# downmixersA.net
KiCad netlist of a schematic drawn in Altium Designer
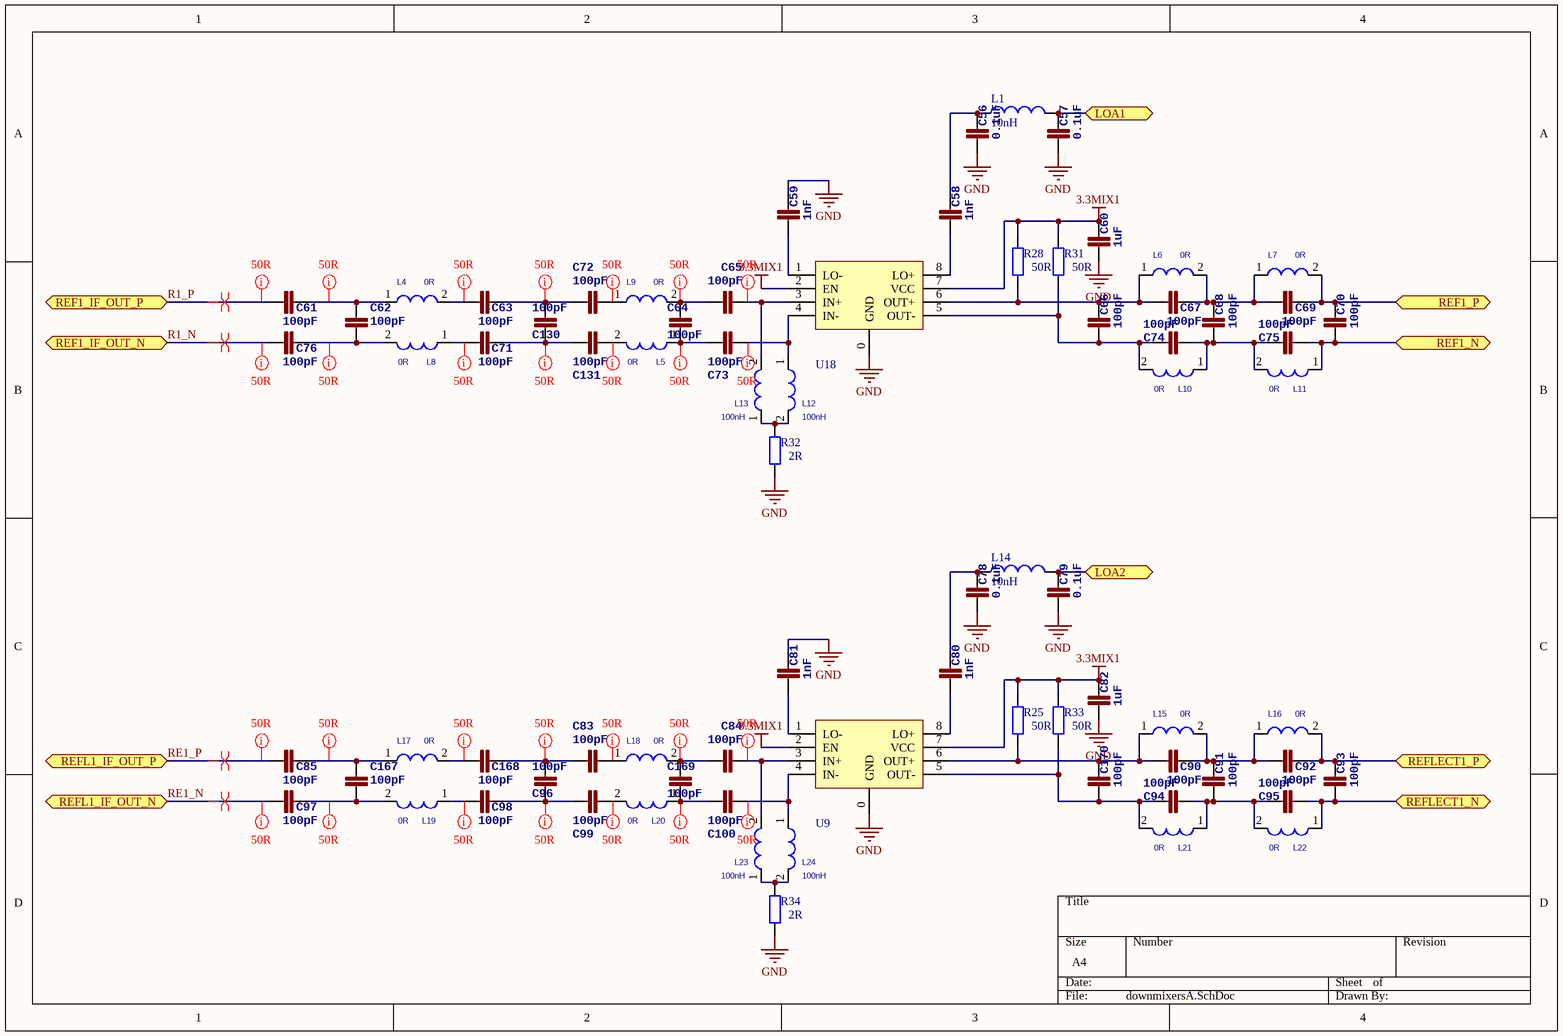
[diagram p0: downmixersA.SchDoc]

(export (version "E")
  (design (tool "Eeschema 10.0.6"))
  (components
    (comp (ref "C56")
      (value "0.1uF")
      (footprint "0402")
      (description "<b>Capacitor</b>\nStandard 0603 ceramic capacitor, and 0.1\" leaded capacitor.")
      (fields (field (name "PARTNO") "CC0402ZRY5V7BB104"))
      (libsource (lib "pixhawk2") (part "CAP0402-CAP"))
    )
    (comp (ref "C57")
      (value "0.1uF")
      (footprint "0402")
      (description "<b>Capacitor</b>\nStandard 0603 ceramic capacitor, and 0.1\" leaded capacitor.")
      (fields (field (name "PARTNO") "CC0402ZRY5V7BB104"))
      (libsource (lib "pixhawk2") (part "CAP0402-CAP"))
    )
    (comp (ref "C58")
      (value "1nF")
      (footprint "0402")
      (description "<b>Capacitor</b>\nStandard 0603 ceramic capacitor, and 0.1\" leaded capacitor.")
      (fields (field (name "PARTNO") "CC0402ZRY5V7BB104"))
      (libsource (lib "pixhawk2") (part "CAP0402-CAP"))
    )
    (comp (ref "C59")
      (value "1nF")
      (footprint "0402")
      (description "<b>Capacitor</b>\nStandard 0603 ceramic capacitor, and 0.1\" leaded capacitor.")
      (fields (field (name "PARTNO") "CC0402ZRY5V7BB104"))
      (libsource (lib "pixhawk2") (part "CAP0402-CAP"))
    )
    (comp (ref "C60")
      (value "1uF")
      (footprint "0402")
      (description "<b>Capacitor</b>\nStandard 0603 ceramic capacitor, and 0.1\" leaded capacitor.")
      (fields (field (name "PARTNO") "CC0402ZRY5V7BB104"))
      (libsource (lib "pixhawk2") (part "CAP0402-CAP"))
    )
    (comp (ref "C61")
      (value "100pF")
      (footprint "0402")
      (description "<b>Capacitor</b>\nStandard 0603 ceramic capacitor, and 0.1\" leaded capacitor.")
      (fields (field (name "PARTNO") "CC0402ZRY5V7BB104"))
      (libsource (lib "") (part "CAP0402-CAP_1"))
    )
    (comp (ref "C62")
      (value "100pF")
      (footprint "0402")
      (description "<b>Capacitor</b>\nStandard 0603 ceramic capacitor, and 0.1\" leaded capacitor.")
      (fields (field (name "PARTNO") "CC0402ZRY5V7BB104"))
      (libsource (lib "pixhawk2") (part "CAP0402-CAP"))
    )
    (comp (ref "C63")
      (value "100pF")
      (footprint "0402")
      (description "<b>Capacitor</b>\nStandard 0603 ceramic capacitor, and 0.1\" leaded capacitor.")
      (fields (field (name "PARTNO") "CC0402ZRY5V7BB104"))
      (libsource (lib "") (part "CAP0402-CAP_1"))
    )
    (comp (ref "C64")
      (value "100pF")
      (footprint "0402")
      (description "<b>Capacitor</b>\nStandard 0603 ceramic capacitor, and 0.1\" leaded capacitor.")
      (fields (field (name "PARTNO") "CC0402ZRY5V7BB104"))
      (libsource (lib "pixhawk2") (part "CAP0402-CAP"))
    )
    (comp (ref "C65")
      (value "100pF")
      (footprint "0402")
      (description "<b>Capacitor</b>\nStandard 0603 ceramic capacitor, and 0.1\" leaded capacitor.")
      (fields (field (name "PARTNO") "CC0402ZRY5V7BB104"))
      (libsource (lib "") (part "CAP0402-CAP_1"))
    )
    (comp (ref "C66")
      (value "100pF")
      (footprint "0402")
      (description "<b>Capacitor</b>\nStandard 0603 ceramic capacitor, and 0.1\" leaded capacitor.")
      (fields (field (name "PARTNO") "CC0402ZRY5V7BB104"))
      (libsource (lib "pixhawk2") (part "CAP0402-CAP"))
    )
    (comp (ref "C67")
      (value "100pF")
      (footprint "0402")
      (description "<b>Capacitor</b>\nStandard 0603 ceramic capacitor, and 0.1\" leaded capacitor.")
      (fields (field (name "PARTNO") "CC0402ZRY5V7BB104"))
      (libsource (lib "") (part "CAP0402-CAP_1"))
    )
    (comp (ref "C68")
      (value "100pF")
      (footprint "0402")
      (description "<b>Capacitor</b>\nStandard 0603 ceramic capacitor, and 0.1\" leaded capacitor.")
      (fields (field (name "PARTNO") "CC0402ZRY5V7BB104"))
      (libsource (lib "pixhawk2") (part "CAP0402-CAP"))
    )
    (comp (ref "C69")
      (value "100pF")
      (footprint "0402")
      (description "<b>Capacitor</b>\nStandard 0603 ceramic capacitor, and 0.1\" leaded capacitor.")
      (fields (field (name "PARTNO") "CC0402ZRY5V7BB104"))
      (libsource (lib "") (part "CAP0402-CAP_1"))
    )
    (comp (ref "C70")
      (value "100pF")
      (footprint "0402")
      (description "<b>Capacitor</b>\nStandard 0603 ceramic capacitor, and 0.1\" leaded capacitor.")
      (fields (field (name "PARTNO") "CC0402ZRY5V7BB104"))
      (libsource (lib "pixhawk2") (part "CAP0402-CAP"))
    )
    (comp (ref "C71")
      (value "100pF")
      (footprint "0402")
      (description "<b>Capacitor</b>\nStandard 0603 ceramic capacitor, and 0.1\" leaded capacitor.")
      (fields (field (name "PARTNO") "CC0402ZRY5V7BB104"))
      (libsource (lib "") (part "CAP0402-CAP_1"))
    )
    (comp (ref "C72")
      (value "100pF")
      (footprint "0402")
      (description "<b>Capacitor</b>\nStandard 0603 ceramic capacitor, and 0.1\" leaded capacitor.")
      (fields (field (name "PARTNO") "CC0402ZRY5V7BB104"))
      (libsource (lib "") (part "CAP0402-CAP_1"))
    )
    (comp (ref "C73")
      (value "100pF")
      (footprint "0402")
      (description "<b>Capacitor</b>\nStandard 0603 ceramic capacitor, and 0.1\" leaded capacitor.")
      (fields (field (name "PARTNO") "CC0402ZRY5V7BB104"))
      (libsource (lib "") (part "CAP0402-CAP_2"))
    )
    (comp (ref "C74")
      (value "100pF")
      (footprint "0402")
      (description "<b>Capacitor</b>\nStandard 0603 ceramic capacitor, and 0.1\" leaded capacitor.")
      (fields (field (name "PARTNO") "CC0402ZRY5V7BB104"))
      (libsource (lib "") (part "CAP0402-CAP_2"))
    )
    (comp (ref "C75")
      (value "100pF")
      (footprint "0402")
      (description "<b>Capacitor</b>\nStandard 0603 ceramic capacitor, and 0.1\" leaded capacitor.")
      (fields (field (name "PARTNO") "CC0402ZRY5V7BB104"))
      (libsource (lib "") (part "CAP0402-CAP_2"))
    )
    (comp (ref "C76")
      (value "100pF")
      (footprint "0402")
      (description "<b>Capacitor</b>\nStandard 0603 ceramic capacitor, and 0.1\" leaded capacitor.")
      (fields (field (name "PARTNO") "CC0402ZRY5V7BB104"))
      (libsource (lib "") (part "CAP0402-CAP_1"))
    )
    (comp (ref "C78")
      (value "0.1uF")
      (footprint "0402")
      (description "<b>Capacitor</b>\nStandard 0603 ceramic capacitor, and 0.1\" leaded capacitor.")
      (fields (field (name "PARTNO") "CC0402ZRY5V7BB104"))
      (libsource (lib "pixhawk2") (part "CAP0402-CAP"))
    )
    (comp (ref "C79")
      (value "0.1uF")
      (footprint "0402")
      (description "<b>Capacitor</b>\nStandard 0603 ceramic capacitor, and 0.1\" leaded capacitor.")
      (fields (field (name "PARTNO") "CC0402ZRY5V7BB104"))
      (libsource (lib "pixhawk2") (part "CAP0402-CAP"))
    )
    (comp (ref "C80")
      (value "1nF")
      (footprint "0402")
      (description "<b>Capacitor</b>\nStandard 0603 ceramic capacitor, and 0.1\" leaded capacitor.")
      (fields (field (name "PARTNO") "CC0402ZRY5V7BB104"))
      (libsource (lib "pixhawk2") (part "CAP0402-CAP"))
    )
    (comp (ref "C81")
      (value "1nF")
      (footprint "0402")
      (description "<b>Capacitor</b>\nStandard 0603 ceramic capacitor, and 0.1\" leaded capacitor.")
      (fields (field (name "PARTNO") "CC0402ZRY5V7BB104"))
      (libsource (lib "pixhawk2") (part "CAP0402-CAP"))
    )
    (comp (ref "C82")
      (value "1uF")
      (footprint "0402")
      (description "<b>Capacitor</b>\nStandard 0603 ceramic capacitor, and 0.1\" leaded capacitor.")
      (fields (field (name "PARTNO") "CC0402ZRY5V7BB104"))
      (libsource (lib "pixhawk2") (part "CAP0402-CAP"))
    )
    (comp (ref "C83")
      (value "100pF")
      (footprint "0402")
      (description "<b>Capacitor</b>\nStandard 0603 ceramic capacitor, and 0.1\" leaded capacitor.")
      (fields (field (name "PARTNO") "CC0402ZRY5V7BB104"))
      (libsource (lib "") (part "CAP0402-CAP_1"))
    )
    (comp (ref "C84")
      (value "100pF")
      (footprint "0402")
      (description "<b>Capacitor</b>\nStandard 0603 ceramic capacitor, and 0.1\" leaded capacitor.")
      (fields (field (name "PARTNO") "CC0402ZRY5V7BB104"))
      (libsource (lib "") (part "CAP0402-CAP_1"))
    )
    (comp (ref "C85")
      (value "100pF")
      (footprint "0402")
      (description "<b>Capacitor</b>\nStandard 0603 ceramic capacitor, and 0.1\" leaded capacitor.")
      (fields (field (name "PARTNO") "CC0402ZRY5V7BB104"))
      (libsource (lib "") (part "CAP0402-CAP_1"))
    )
    (comp (ref "C90")
      (value "100pF")
      (footprint "0402")
      (description "<b>Capacitor</b>\nStandard 0603 ceramic capacitor, and 0.1\" leaded capacitor.")
      (fields (field (name "PARTNO") "CC0402ZRY5V7BB104"))
      (libsource (lib "") (part "CAP0402-CAP_1"))
    )
    (comp (ref "C91")
      (value "100pF")
      (footprint "0402")
      (description "<b>Capacitor</b>\nStandard 0603 ceramic capacitor, and 0.1\" leaded capacitor.")
      (fields (field (name "PARTNO") "CC0402ZRY5V7BB104"))
      (libsource (lib "pixhawk2") (part "CAP0402-CAP"))
    )
    (comp (ref "C92")
      (value "100pF")
      (footprint "0402")
      (description "<b>Capacitor</b>\nStandard 0603 ceramic capacitor, and 0.1\" leaded capacitor.")
      (fields (field (name "PARTNO") "CC0402ZRY5V7BB104"))
      (libsource (lib "") (part "CAP0402-CAP_1"))
    )
    (comp (ref "C93")
      (value "100pF")
      (footprint "0402")
      (description "<b>Capacitor</b>\nStandard 0603 ceramic capacitor, and 0.1\" leaded capacitor.")
      (fields (field (name "PARTNO") "CC0402ZRY5V7BB104"))
      (libsource (lib "pixhawk2") (part "CAP0402-CAP"))
    )
    (comp (ref "C94")
      (value "100pF")
      (footprint "0402")
      (description "<b>Capacitor</b>\nStandard 0603 ceramic capacitor, and 0.1\" leaded capacitor.")
      (fields (field (name "PARTNO") "CC0402ZRY5V7BB104"))
      (libsource (lib "") (part "CAP0402-CAP_2"))
    )
    (comp (ref "C95")
      (value "100pF")
      (footprint "0402")
      (description "<b>Capacitor</b>\nStandard 0603 ceramic capacitor, and 0.1\" leaded capacitor.")
      (fields (field (name "PARTNO") "CC0402ZRY5V7BB104"))
      (libsource (lib "") (part "CAP0402-CAP_2"))
    )
    (comp (ref "C96")
      (value "100pF")
      (footprint "0402")
      (description "<b>Capacitor</b>\nStandard 0603 ceramic capacitor, and 0.1\" leaded capacitor.")
      (fields (field (name "PARTNO") "CC0402ZRY5V7BB104"))
      (libsource (lib "") (part "CAP0402-CAP_3"))
    )
    (comp (ref "C97")
      (value "100pF")
      (footprint "0402")
      (description "<b>Capacitor</b>\nStandard 0603 ceramic capacitor, and 0.1\" leaded capacitor.")
      (fields (field (name "PARTNO") "CC0402ZRY5V7BB104"))
      (libsource (lib "") (part "CAP0402-CAP_1"))
    )
    (comp (ref "C98")
      (value "100pF")
      (footprint "0402")
      (description "<b>Capacitor</b>\nStandard 0603 ceramic capacitor, and 0.1\" leaded capacitor.")
      (fields (field (name "PARTNO") "CC0402ZRY5V7BB104"))
      (libsource (lib "") (part "CAP0402-CAP_1"))
    )
    (comp (ref "C99")
      (value "100pF")
      (footprint "0402")
      (description "<b>Capacitor</b>\nStandard 0603 ceramic capacitor, and 0.1\" leaded capacitor.")
      (fields (field (name "PARTNO") "CC0402ZRY5V7BB104"))
      (libsource (lib "") (part "CAP0402-CAP_2"))
    )
    (comp (ref "C100")
      (value "100pF")
      (footprint "0402")
      (description "<b>Capacitor</b>\nStandard 0603 ceramic capacitor, and 0.1\" leaded capacitor.")
      (fields (field (name "PARTNO") "CC0402ZRY5V7BB104"))
      (libsource (lib "") (part "CAP0402-CAP_2"))
    )
    (comp (ref "C130")
      (value "100pF")
      (footprint "0402")
      (description "<b>Capacitor</b>\nStandard 0603 ceramic capacitor, and 0.1\" leaded capacitor.")
      (fields (field (name "PARTNO") "CC0402ZRY5V7BB104"))
      (libsource (lib "") (part "CAP0402-CAP_3"))
    )
    (comp (ref "C131")
      (value "100pF")
      (footprint "0402")
      (description "<b>Capacitor</b>\nStandard 0603 ceramic capacitor, and 0.1\" leaded capacitor.")
      (fields (field (name "PARTNO") "CC0402ZRY5V7BB104"))
      (libsource (lib "") (part "CAP0402-CAP_2"))
    )
    (comp (ref "C167")
      (value "100pF")
      (footprint "0402")
      (description "<b>Capacitor</b>\nStandard 0603 ceramic capacitor, and 0.1\" leaded capacitor.")
      (fields (field (name "PARTNO") "CC0402ZRY5V7BB104"))
      (libsource (lib "pixhawk2") (part "CAP0402-CAP"))
    )
    (comp (ref "C168")
      (value "100pF")
      (footprint "0402")
      (description "<b>Capacitor</b>\nStandard 0603 ceramic capacitor, and 0.1\" leaded capacitor.")
      (fields (field (name "PARTNO") "CC0402ZRY5V7BB104"))
      (libsource (lib "") (part "CAP0402-CAP_1"))
    )
    (comp (ref "C169")
      (value "100pF")
      (footprint "0402")
      (description "<b>Capacitor</b>\nStandard 0603 ceramic capacitor, and 0.1\" leaded capacitor.")
      (fields (field (name "PARTNO") "CC0402ZRY5V7BB104"))
      (libsource (lib "pixhawk2") (part "CAP0402-CAP"))
    )
    (comp (ref "C170")
      (value "100pF")
      (footprint "0402")
      (description "<b>Capacitor</b>\nStandard 0603 ceramic capacitor, and 0.1\" leaded capacitor.")
      (fields (field (name "PARTNO") "CC0402ZRY5V7BB104"))
      (libsource (lib "pixhawk2") (part "CAP0402-CAP"))
    )
    (comp (ref "L1")
      (value "10nH")
      (footprint "0402")
      (description "Inductor")
      (fields (field (name "PUBLISHER") "Altium Limited"))
      (libsource (lib "Miscellaneous Devices") (part "Inductor"))
    )
    (comp (ref "L4") (value "0R") (footprint "0805") (libsource (lib "*") (part "L/2.5*2.0")))
    (comp (ref "L5") (value "0R") (footprint "0805") (libsource (lib "*") (part "L/2.5*2.0")))
    (comp (ref "L6") (value "0R") (footprint "0805") (libsource (lib "*") (part "L/2.5*2.0")))
    (comp (ref "L7") (value "0R") (footprint "0805") (libsource (lib "*") (part "L/2.5*2.0")))
    (comp (ref "L8") (value "0R") (footprint "0805") (libsource (lib "*") (part "L/2.5*2.0")))
    (comp (ref "L9") (value "0R") (footprint "0805") (libsource (lib "*") (part "L/2.5*2.0")))
    (comp (ref "L10") (value "0R") (footprint "0805") (libsource (lib "*") (part "L/2.5*2.0")))
    (comp (ref "L11") (value "0R") (footprint "0805") (libsource (lib "*") (part "L/2.5*2.0")))
    (comp (ref "L12") (value "100nH") (footprint "0402") (libsource (lib "*") (part "L/2.5*2.0")))
    (comp (ref "L13") (value "100nH") (footprint "0402") (libsource (lib "*") (part "L/2.5*2.0")))
    (comp (ref "L14")
      (value "10nH")
      (footprint "0402")
      (description "Inductor")
      (fields (field (name "PUBLISHER") "Altium Limited"))
      (libsource (lib "Miscellaneous Devices") (part "Inductor"))
    )
    (comp (ref "L15") (value "0R") (footprint "0805") (libsource (lib "*") (part "L/2.5*2.0")))
    (comp (ref "L16") (value "0R") (footprint "0805") (libsource (lib "*") (part "L/2.5*2.0")))
    (comp (ref "L17") (value "0R") (footprint "0805") (libsource (lib "*") (part "L/2.5*2.0")))
    (comp (ref "L18") (value "0R") (footprint "0805") (libsource (lib "*") (part "L/2.5*2.0")))
    (comp (ref "L19") (value "0R") (footprint "0805") (libsource (lib "*") (part "L/2.5*2.0")))
    (comp (ref "L20") (value "0R") (footprint "0805") (libsource (lib "*") (part "L/2.5*2.0")))
    (comp (ref "L21") (value "0R") (footprint "0805") (libsource (lib "*") (part "L/2.5*2.0")))
    (comp (ref "L22") (value "0R") (footprint "0805") (libsource (lib "*") (part "L/2.5*2.0")))
    (comp (ref "L23") (value "100nH") (footprint "0402") (libsource (lib "*") (part "L/2.5*2.0")))
    (comp (ref "L24") (value "100nH") (footprint "0402") (libsource (lib "*") (part "L/2.5*2.0")))
    (comp (ref "R25")
      (value "50R")
      (footprint "0402")
      (description "Resistor")
      (libsource (lib "RTC6705") (part "Res2"))
    )
    (comp (ref "R28")
      (value "50R")
      (footprint "0402")
      (description "Resistor")
      (libsource (lib "RTC6705") (part "Res2"))
    )
    (comp (ref "R31")
      (value "50R")
      (footprint "0402")
      (description "Resistor")
      (libsource (lib "RTC6705") (part "Res2"))
    )
    (comp (ref "R32")
      (value "2R")
      (footprint "0402")
      (description "Resistor")
      (libsource (lib "RTC6705") (part "Res2"))
    )
    (comp (ref "R33")
      (value "50R")
      (footprint "0402")
      (description "Resistor")
      (libsource (lib "RTC6705") (part "Res2"))
    )
    (comp (ref "R34")
      (value "2R")
      (footprint "0402")
      (description "Resistor")
      (libsource (lib "RTC6705") (part "Res2"))
    )
    (comp (ref "U9") (value "LT5560") (footprint "LT5560") (libsource (lib "F4SDR") (part "LT5560")))
    (comp (ref "U18") (value "LT5560") (footprint "LT5560") (libsource (lib "F4SDR") (part "LT5560")))
  )
  (nets
    (net (code "1") (name "/LOA1") (class "Default")
      (node (ref "C57") (pin "2") (pinfunction "2_2") (pintype "passive"))
      (node (ref "L1") (pin "2") (pinfunction "2_2") (pintype "passive"))
    )
    (net (code "2") (name "/LOA2") (class "Default")
      (node (ref "C79") (pin "2") (pinfunction "2_2") (pintype "passive"))
      (node (ref "L14") (pin "2") (pinfunction "2_2") (pintype "passive"))
    )
    (net (code "3") (name "/R1_N") (class "Default")
      (node (ref "C76") (pin "1") (pinfunction "1_1") (pintype "passive"))
    )
    (net (code "4") (name "/R1_P") (class "Default")
      (node (ref "C61") (pin "1") (pinfunction "1_1") (pintype "passive"))
    )
    (net (code "5") (name "/RE1_N") (class "Default")
      (node (ref "C97") (pin "1") (pinfunction "1_1") (pintype "passive"))
    )
    (net (code "6") (name "/RE1_P") (class "Default")
      (node (ref "C85") (pin "1") (pinfunction "1_1") (pintype "passive"))
    )
    (net (code "7") (name "/REF1_N") (class "Default")
      (node (ref "C70") (pin "1") (pinfunction "1_1") (pintype "passive"))
      (node (ref "C75") (pin "1") (pinfunction "1_1") (pintype "passive"))
      (node (ref "L11") (pin "1") (pinfunction "1_1") (pintype "passive"))
    )
    (net (code "8") (name "/REF1_P") (class "Default")
      (node (ref "C69") (pin "2") (pinfunction "2_2") (pintype "passive"))
      (node (ref "C70") (pin "2") (pinfunction "2_2") (pintype "passive"))
      (node (ref "L7") (pin "2") (pinfunction "2_2") (pintype "passive"))
    )
    (net (code "9") (name "/REFLECT1_N") (class "Default")
      (node (ref "C93") (pin "1") (pinfunction "1_1") (pintype "passive"))
      (node (ref "C95") (pin "1") (pinfunction "1_1") (pintype "passive"))
      (node (ref "L22") (pin "1") (pinfunction "1_1") (pintype "passive"))
    )
    (net (code "10") (name "/REFLECT1_P") (class "Default")
      (node (ref "C92") (pin "2") (pinfunction "2_2") (pintype "passive"))
      (node (ref "C93") (pin "2") (pinfunction "2_2") (pintype "passive"))
      (node (ref "L16") (pin "2") (pinfunction "2_2") (pintype "passive"))
    )
    (net (code "11") (name "3.3MIX1") (class "Default")
      (node (ref "C60") (pin "2") (pinfunction "2_2") (pintype "passive"))
      (node (ref "C82") (pin "2") (pinfunction "2_2") (pintype "passive"))
      (node (ref "R25") (pin "2") (pinfunction "2_2") (pintype "passive"))
      (node (ref "R28") (pin "2") (pinfunction "2_2") (pintype "passive"))
      (node (ref "R31") (pin "2") (pinfunction "2_2") (pintype "passive"))
      (node (ref "R33") (pin "2") (pinfunction "2_2") (pintype "passive"))
      (node (ref "U18") (pin "2") (pinfunction "EN_2") (pintype "passive"))
      (node (ref "U18") (pin "7") (pinfunction "VCC_7") (pintype "passive"))
      (node (ref "U9") (pin "2") (pinfunction "EN_2") (pintype "passive"))
      (node (ref "U9") (pin "7") (pinfunction "VCC_7") (pintype "passive"))
    )
    (net (code "12") (name "GND") (class "Default")
      (node (ref "C56") (pin "1") (pinfunction "1_1") (pintype "passive"))
      (node (ref "C57") (pin "1") (pinfunction "1_1") (pintype "passive"))
      (node (ref "C59") (pin "2") (pinfunction "2_2") (pintype "passive"))
      (node (ref "C60") (pin "1") (pinfunction "1_1") (pintype "passive"))
      (node (ref "C78") (pin "1") (pinfunction "1_1") (pintype "passive"))
      (node (ref "C79") (pin "1") (pinfunction "1_1") (pintype "passive"))
      (node (ref "C81") (pin "2") (pinfunction "2_2") (pintype "passive"))
      (node (ref "C82") (pin "1") (pinfunction "1_1") (pintype "passive"))
      (node (ref "R32") (pin "1") (pinfunction "1_1") (pintype "passive"))
      (node (ref "R34") (pin "1") (pinfunction "1_1") (pintype "passive"))
      (node (ref "U18") (pin "0") (pinfunction "GND_0") (pintype "passive"))
      (node (ref "U9") (pin "0") (pinfunction "GND_0") (pintype "passive"))
    )
    (net (code "13") (name "Net-(C56-Pad2)") (class "Default")
      (node (ref "C56") (pin "2") (pinfunction "2_2") (pintype "passive"))
      (node (ref "C58") (pin "2") (pinfunction "2_2") (pintype "passive"))
      (node (ref "L1") (pin "1") (pinfunction "1_1") (pintype "passive"))
    )
    (net (code "14") (name "Net-(C61-Pad2)") (class "Default")
      (node (ref "C61") (pin "2") (pinfunction "2_2") (pintype "passive"))
      (node (ref "C62") (pin "2") (pinfunction "2_2") (pintype "passive"))
      (node (ref "L4") (pin "1") (pinfunction "1_1") (pintype "passive"))
    )
    (net (code "15") (name "Net-(C62-Pad1)") (class "Default")
      (node (ref "C62") (pin "1") (pinfunction "1_1") (pintype "passive"))
      (node (ref "C76") (pin "2") (pinfunction "2_2") (pintype "passive"))
      (node (ref "L8") (pin "2") (pinfunction "2_2") (pintype "passive"))
    )
    (net (code "16") (name "Net-(C63-Pad1)") (class "Default")
      (node (ref "C63") (pin "1") (pinfunction "1_1") (pintype "passive"))
      (node (ref "L4") (pin "2") (pinfunction "2_2") (pintype "passive"))
    )
    (net (code "17") (name "Net-(C64-Pad1)") (class "Default")
      (node (ref "C64") (pin "1") (pinfunction "1_1") (pintype "passive"))
      (node (ref "C73") (pin "2") (pinfunction "2_2") (pintype "passive"))
      (node (ref "L5") (pin "1") (pinfunction "1_1") (pintype "passive"))
    )
    (net (code "18") (name "Net-(C64-Pad2)") (class "Default")
      (node (ref "C64") (pin "2") (pinfunction "2_2") (pintype "passive"))
      (node (ref "C65") (pin "1") (pinfunction "1_1") (pintype "passive"))
      (node (ref "L9") (pin "2") (pinfunction "2_2") (pintype "passive"))
    )
    (net (code "19") (name "Net-(C67-Pad2)") (class "Default")
      (node (ref "C67") (pin "2") (pinfunction "2_2") (pintype "passive"))
      (node (ref "C68") (pin "2") (pinfunction "2_2") (pintype "passive"))
      (node (ref "C69") (pin "1") (pinfunction "1_1") (pintype "passive"))
      (node (ref "L6") (pin "2") (pinfunction "2_2") (pintype "passive"))
      (node (ref "L7") (pin "1") (pinfunction "1_1") (pintype "passive"))
    )
    (net (code "20") (name "Net-(C68-Pad1)") (class "Default")
      (node (ref "C68") (pin "1") (pinfunction "1_1") (pintype "passive"))
      (node (ref "C74") (pin "1") (pinfunction "1_1") (pintype "passive"))
      (node (ref "C75") (pin "2") (pinfunction "2_2") (pintype "passive"))
      (node (ref "L10") (pin "1") (pinfunction "1_1") (pintype "passive"))
      (node (ref "L11") (pin "2") (pinfunction "2_2") (pintype "passive"))
    )
    (net (code "21") (name "Net-(C71-Pad1)") (class "Default")
      (node (ref "C71") (pin "1") (pinfunction "1_1") (pintype "passive"))
      (node (ref "L8") (pin "1") (pinfunction "1_1") (pintype "passive"))
    )
    (net (code "22") (name "Net-(C72-Pad2)") (class "Default")
      (node (ref "C72") (pin "2") (pinfunction "2_2") (pintype "passive"))
      (node (ref "L9") (pin "1") (pinfunction "1_1") (pintype "passive"))
    )
    (net (code "23") (name "Net-(C78-Pad2)") (class "Default")
      (node (ref "C78") (pin "2") (pinfunction "2_2") (pintype "passive"))
      (node (ref "C80") (pin "2") (pinfunction "2_2") (pintype "passive"))
      (node (ref "L14") (pin "1") (pinfunction "1_1") (pintype "passive"))
    )
    (net (code "24") (name "Net-(C83-Pad2)") (class "Default")
      (node (ref "C83") (pin "2") (pinfunction "2_2") (pintype "passive"))
      (node (ref "L18") (pin "1") (pinfunction "1_1") (pintype "passive"))
    )
    (net (code "25") (name "Net-(C90-Pad2)") (class "Default")
      (node (ref "C90") (pin "2") (pinfunction "2_2") (pintype "passive"))
      (node (ref "C91") (pin "2") (pinfunction "2_2") (pintype "passive"))
      (node (ref "C92") (pin "1") (pinfunction "1_1") (pintype "passive"))
      (node (ref "L15") (pin "2") (pinfunction "2_2") (pintype "passive"))
      (node (ref "L16") (pin "1") (pinfunction "1_1") (pintype "passive"))
    )
    (net (code "26") (name "Net-(C91-Pad1)") (class "Default")
      (node (ref "C91") (pin "1") (pinfunction "1_1") (pintype "passive"))
      (node (ref "C94") (pin "1") (pinfunction "1_1") (pintype "passive"))
      (node (ref "C95") (pin "2") (pinfunction "2_2") (pintype "passive"))
      (node (ref "L21") (pin "1") (pinfunction "1_1") (pintype "passive"))
      (node (ref "L22") (pin "2") (pinfunction "2_2") (pintype "passive"))
    )
    (net (code "27") (name "Net-(C96-Pad2)") (class "Default")
      (node (ref "C96") (pin "2") (pinfunction "2_2") (pintype "passive"))
      (node (ref "C98") (pin "2") (pinfunction "2_2") (pintype "passive"))
      (node (ref "C99") (pin "2") (pinfunction "2_2") (pintype "passive"))
    )
    (net (code "28") (name "Net-(C98-Pad1)") (class "Default")
      (node (ref "C98") (pin "1") (pinfunction "1_1") (pintype "passive"))
      (node (ref "L19") (pin "1") (pinfunction "1_1") (pintype "passive"))
    )
    (net (code "29") (name "Net-(C99-Pad1)") (class "Default")
      (node (ref "C99") (pin "1") (pinfunction "1_1") (pintype "passive"))
      (node (ref "L20") (pin "2") (pinfunction "2_2") (pintype "passive"))
    )
    (net (code "30") (name "Net-(C100-Pad2)") (class "Default")
      (node (ref "C100") (pin "2") (pinfunction "2_2") (pintype "passive"))
      (node (ref "C169") (pin "1") (pinfunction "1_1") (pintype "passive"))
      (node (ref "L20") (pin "1") (pinfunction "1_1") (pintype "passive"))
    )
    (net (code "31") (name "Net-(C130-Pad1)") (class "Default")
      (node (ref "C130") (pin "1") (pinfunction "1_1") (pintype "passive"))
      (node (ref "C63") (pin "2") (pinfunction "2_2") (pintype "passive"))
      (node (ref "C72") (pin "1") (pinfunction "1_1") (pintype "passive"))
    )
    (net (code "32") (name "Net-(C130-Pad2)") (class "Default")
      (node (ref "C130") (pin "2") (pinfunction "2_2") (pintype "passive"))
      (node (ref "C131") (pin "2") (pinfunction "2_2") (pintype "passive"))
      (node (ref "C71") (pin "2") (pinfunction "2_2") (pintype "passive"))
    )
    (net (code "33") (name "Net-(C131-Pad1)") (class "Default")
      (node (ref "C131") (pin "1") (pinfunction "1_1") (pintype "passive"))
      (node (ref "L5") (pin "2") (pinfunction "2_2") (pintype "passive"))
    )
    (net (code "34") (name "Net-(C167-Pad1)") (class "Default")
      (node (ref "C167") (pin "1") (pinfunction "1_1") (pintype "passive"))
      (node (ref "C97") (pin "2") (pinfunction "2_2") (pintype "passive"))
      (node (ref "L19") (pin "2") (pinfunction "2_2") (pintype "passive"))
    )
    (net (code "35") (name "Net-(C167-Pad2)") (class "Default")
      (node (ref "C167") (pin "2") (pinfunction "2_2") (pintype "passive"))
      (node (ref "C85") (pin "2") (pinfunction "2_2") (pintype "passive"))
      (node (ref "L17") (pin "1") (pinfunction "1_1") (pintype "passive"))
    )
    (net (code "36") (name "Net-(C168-Pad1)") (class "Default")
      (node (ref "C168") (pin "1") (pinfunction "1_1") (pintype "passive"))
      (node (ref "L17") (pin "2") (pinfunction "2_2") (pintype "passive"))
    )
    (net (code "37") (name "Net-(C168-Pad2)") (class "Default")
      (node (ref "C168") (pin "2") (pinfunction "2_2") (pintype "passive"))
      (node (ref "C83") (pin "1") (pinfunction "1_1") (pintype "passive"))
      (node (ref "C96") (pin "1") (pinfunction "1_1") (pintype "passive"))
    )
    (net (code "38") (name "Net-(C169-Pad2)") (class "Default")
      (node (ref "C169") (pin "2") (pinfunction "2_2") (pintype "passive"))
      (node (ref "C84") (pin "1") (pinfunction "1_1") (pintype "passive"))
      (node (ref "L18") (pin "2") (pinfunction "2_2") (pintype "passive"))
    )
    (net (code "39") (name "Net-(L12-Pad2)") (class "Default")
      (node (ref "L12") (pin "2") (pinfunction "2_2") (pintype "passive"))
      (node (ref "L13") (pin "1") (pinfunction "1_1") (pintype "passive"))
      (node (ref "R32") (pin "2") (pinfunction "2_2") (pintype "passive"))
    )
    (net (code "40") (name "Net-(L23-Pad1)") (class "Default")
      (node (ref "L23") (pin "1") (pinfunction "1_1") (pintype "passive"))
      (node (ref "L24") (pin "2") (pinfunction "2_2") (pintype "passive"))
      (node (ref "R34") (pin "2") (pinfunction "2_2") (pintype "passive"))
    )
    (net (code "41") (name "Net-(U9-IN+)") (class "Default")
      (node (ref "C84") (pin "2") (pinfunction "2_2") (pintype "passive"))
      (node (ref "L23") (pin "2") (pinfunction "2_2") (pintype "passive"))
      (node (ref "U9") (pin "3") (pinfunction "IN+_3") (pintype "passive"))
    )
    (net (code "42") (name "Net-(U9-IN-)") (class "Default")
      (node (ref "C100") (pin "1") (pinfunction "1_1") (pintype "passive"))
      (node (ref "L24") (pin "1") (pinfunction "1_1") (pintype "passive"))
      (node (ref "U9") (pin "4") (pinfunction "IN-_4") (pintype "passive"))
    )
    (net (code "43") (name "Net-(U9-LO+)") (class "Default")
      (node (ref "C80") (pin "1") (pinfunction "1_1") (pintype "passive"))
      (node (ref "U9") (pin "8") (pinfunction "LO+_8") (pintype "passive"))
    )
    (net (code "44") (name "Net-(U9-LO-)") (class "Default")
      (node (ref "C81") (pin "1") (pinfunction "1_1") (pintype "passive"))
      (node (ref "U9") (pin "1") (pinfunction "LO-_1") (pintype "passive"))
    )
    (net (code "45") (name "Net-(U9-OUT+)") (class "Default")
      (node (ref "C170") (pin "2") (pinfunction "2_2") (pintype "passive"))
      (node (ref "C90") (pin "1") (pinfunction "1_1") (pintype "passive"))
      (node (ref "L15") (pin "1") (pinfunction "1_1") (pintype "passive"))
      (node (ref "R25") (pin "1") (pinfunction "1_1") (pintype "passive"))
      (node (ref "U9") (pin "6") (pinfunction "OUT+_6") (pintype "passive"))
    )
    (net (code "46") (name "Net-(U9-OUT-)") (class "Default")
      (node (ref "C170") (pin "1") (pinfunction "1_1") (pintype "passive"))
      (node (ref "C94") (pin "2") (pinfunction "2_2") (pintype "passive"))
      (node (ref "L21") (pin "2") (pinfunction "2_2") (pintype "passive"))
      (node (ref "R33") (pin "1") (pinfunction "1_1") (pintype "passive"))
      (node (ref "U9") (pin "5") (pinfunction "OUT-_5") (pintype "passive"))
    )
    (net (code "47") (name "Net-(U18-IN+)") (class "Default")
      (node (ref "C65") (pin "2") (pinfunction "2_2") (pintype "passive"))
      (node (ref "L13") (pin "2") (pinfunction "2_2") (pintype "passive"))
      (node (ref "U18") (pin "3") (pinfunction "IN+_3") (pintype "passive"))
    )
    (net (code "48") (name "Net-(U18-IN-)") (class "Default")
      (node (ref "C73") (pin "1") (pinfunction "1_1") (pintype "passive"))
      (node (ref "L12") (pin "1") (pinfunction "1_1") (pintype "passive"))
      (node (ref "U18") (pin "4") (pinfunction "IN-_4") (pintype "passive"))
    )
    (net (code "49") (name "Net-(U18-LO+)") (class "Default")
      (node (ref "C58") (pin "1") (pinfunction "1_1") (pintype "passive"))
      (node (ref "U18") (pin "8") (pinfunction "LO+_8") (pintype "passive"))
    )
    (net (code "50") (name "Net-(U18-LO-)") (class "Default")
      (node (ref "C59") (pin "1") (pinfunction "1_1") (pintype "passive"))
      (node (ref "U18") (pin "1") (pinfunction "LO-_1") (pintype "passive"))
    )
    (net (code "51") (name "Net-(U18-OUT+)") (class "Default")
      (node (ref "C66") (pin "2") (pinfunction "2_2") (pintype "passive"))
      (node (ref "C67") (pin "1") (pinfunction "1_1") (pintype "passive"))
      (node (ref "L6") (pin "1") (pinfunction "1_1") (pintype "passive"))
      (node (ref "R28") (pin "1") (pinfunction "1_1") (pintype "passive"))
      (node (ref "U18") (pin "6") (pinfunction "OUT+_6") (pintype "passive"))
    )
    (net (code "52") (name "Net-(U18-OUT-)") (class "Default")
      (node (ref "C66") (pin "1") (pinfunction "1_1") (pintype "passive"))
      (node (ref "C74") (pin "2") (pinfunction "2_2") (pintype "passive"))
      (node (ref "L10") (pin "2") (pinfunction "2_2") (pintype "passive"))
      (node (ref "R31") (pin "1") (pinfunction "1_1") (pintype "passive"))
      (node (ref "U18") (pin "5") (pinfunction "OUT-_5") (pintype "passive"))
    )
  )
)
